# sheet1.net
KiCad netlist of a schematic drawn in Altium Designer
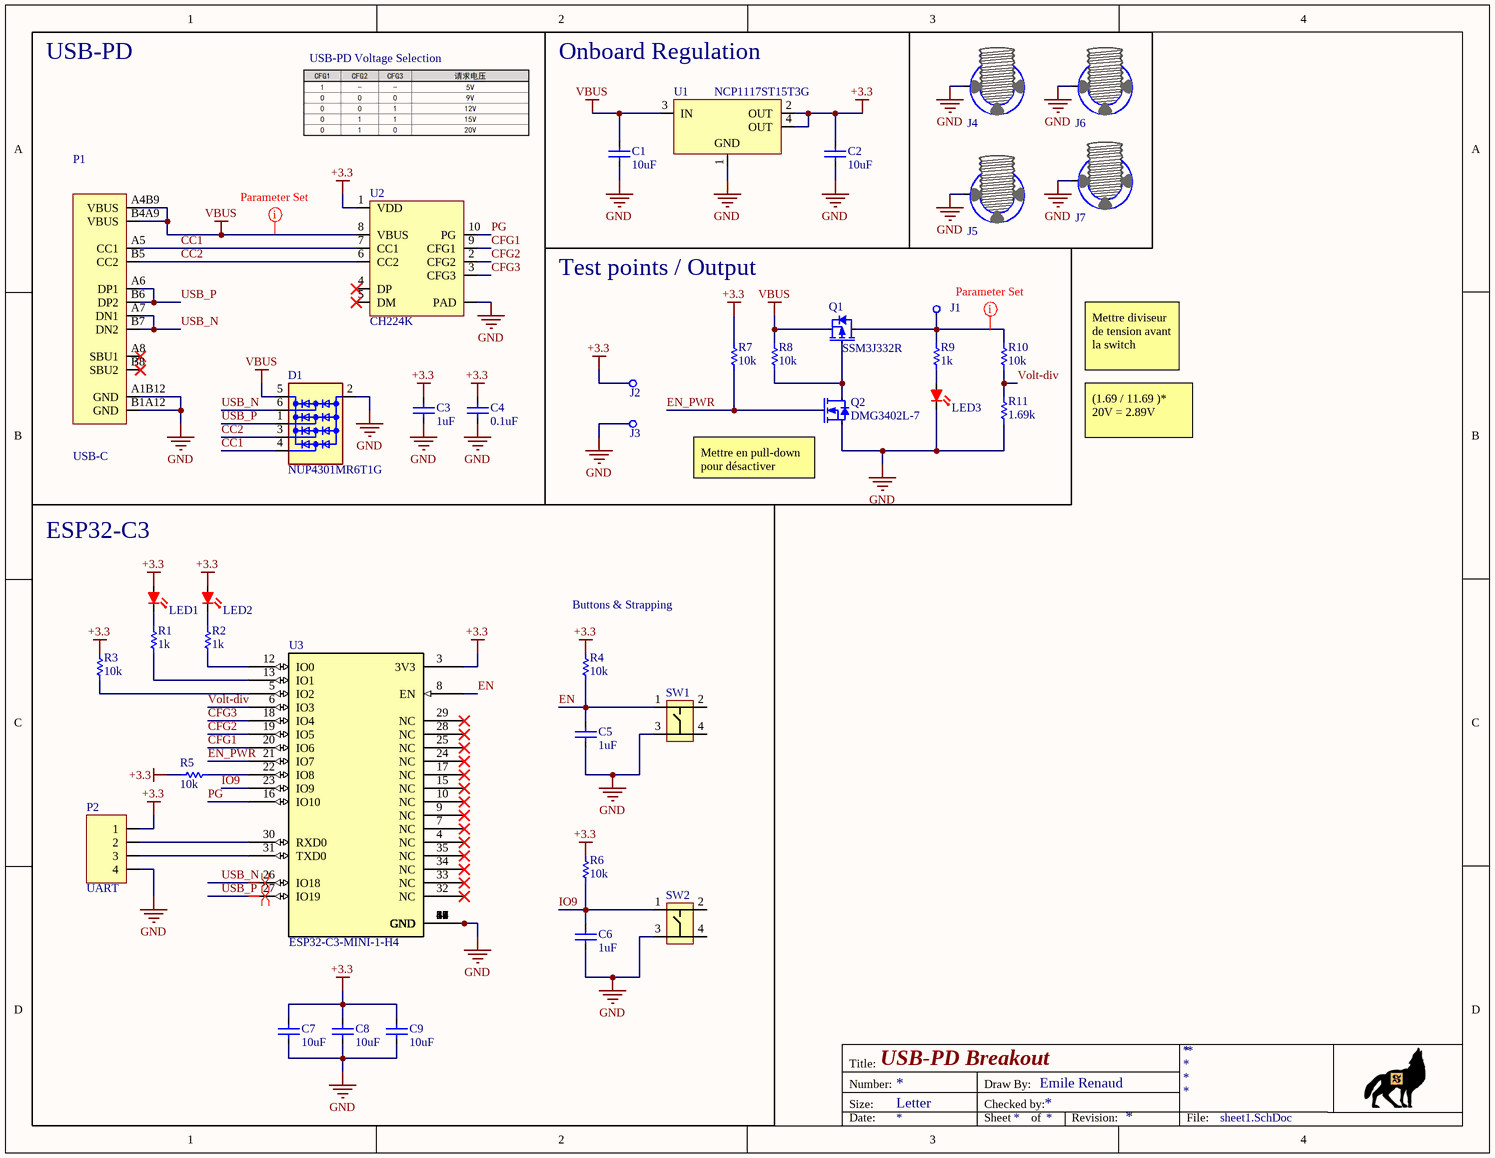
[diagram p0: sheet1.SchDoc]

(export (version "E")
  (design (tool "Eeschema 10.0.6"))
  (components
    (comp (ref "C1")
      (value "10uF")
      (footprint "CAPACITOR-0805")
      (description "Capacitor-0805-10uF-35V-X5R")
      (libsource (lib "Capacitors") (part "Capacitor-0805-10uF-35V-X5R"))
    )
    (comp (ref "C2")
      (value "10uF")
      (footprint "CAPACITOR-0805")
      (description "Capacitor-0805-10uF-35V-X5R")
      (libsource (lib "Capacitors") (part "Capacitor-0805-10uF-35V-X5R"))
    )
    (comp (ref "C3")
      (value "1uF")
      (footprint "CAPACITOR-0603")
      (description "Capacitor-0603-1uF-25V-X5R")
      (libsource (lib "Capacitors") (part "Capacitor-0603-1uF-25V-X5R"))
    )
    (comp (ref "C4")
      (value "0.1uF")
      (footprint "CAPACITOR-0603")
      (description "Capacitor-0603-0.1uF-50V-X7R")
      (libsource (lib "Capacitors") (part "Capacitor-0603-0.1uF-50V-X7R"))
    )
    (comp (ref "C5")
      (value "1uF")
      (footprint "CAPACITOR-0603")
      (description "Capacitor-0603-1uF-25V-X5R")
      (libsource (lib "Capacitors") (part "Capacitor-0603-1uF-25V-X5R"))
    )
    (comp (ref "C6")
      (value "1uF")
      (footprint "CAPACITOR-0603")
      (description "Capacitor-0603-1uF-25V-X5R")
      (libsource (lib "Capacitors") (part "Capacitor-0603-1uF-25V-X5R"))
    )
    (comp (ref "C7")
      (value "10uF")
      (footprint "CAPACITOR-0805")
      (description "Capacitor-0805-10uF-35V-X5R")
      (libsource (lib "Capacitors") (part "Capacitor-0805-10uF-35V-X5R"))
    )
    (comp (ref "C8")
      (value "10uF")
      (footprint "CAPACITOR-0805")
      (description "Capacitor-0805-10uF-35V-X5R")
      (libsource (lib "Capacitors") (part "Capacitor-0805-10uF-35V-X5R"))
    )
    (comp (ref "C9")
      (value "10uF")
      (footprint "CAPACITOR-0805")
      (description "Capacitor-0805-10uF-35V-X5R")
      (libsource (lib "Capacitors") (part "Capacitor-0805-10uF-35V-X5R"))
    )
    (comp (ref "D1")
      (value "NUP4301MR6T1G")
      (footprint "SOT-23-6")
      (description "4CH Clamp Ipp Tvs Diode Surface Mount SOT23-6 (SC74)")
      (libsource (lib "diodes") (part "NUP4301MR6T1G"))
    )
    (comp (ref "J1")
      (value "hole")
      (footprint "HOLE-2.70MM")
      (description "Hole for 12 AWG Stranded Wire")
      (libsource (lib "JumpersAndHoles") (part "Hole 2.70mm AWG12-Stranded"))
    )
    (comp (ref "J2")
      (value "hole")
      (footprint "HOLE-2.70MM")
      (description "Hole for 12 AWG Stranded Wire")
      (libsource (lib "JumpersAndHoles") (part "Hole 2.70mm AWG12-Stranded"))
    )
    (comp (ref "J3")
      (value "hole")
      (footprint "HOLE-2.70MM")
      (description "Hole for 12 AWG Stranded Wire")
      (libsource (lib "JumpersAndHoles") (part "Hole 2.70mm AWG12-Stranded"))
    )
    (comp (ref "J4")
      (value "hole")
      (footprint "HOLE-3.40MM-M3-7MMEYELET-MountingFeature")
      (description "Hole for M3 Bolt with 7mm pad")
      (libsource (lib "JumpersAndHoles") (part "Hole 3.40mm M3-MountingFeature"))
    )
    (comp (ref "J5")
      (value "hole")
      (footprint "HOLE-3.40MM-M3-7MMEYELET-MountingFeature")
      (description "Hole for M3 Bolt with 7mm pad")
      (libsource (lib "JumpersAndHoles") (part "Hole 3.40mm M3-MountingFeature"))
    )
    (comp (ref "J6")
      (value "hole")
      (footprint "HOLE-3.40MM-M3-7MMEYELET-MountingFeature")
      (description "Hole for M3 Bolt with 7mm pad")
      (libsource (lib "JumpersAndHoles") (part "Hole 3.40mm M3-MountingFeature"))
    )
    (comp (ref "J7")
      (value "hole")
      (footprint "HOLE-3.40MM-M3-7MMEYELET-MountingFeature")
      (description "Hole for M3 Bolt with 7mm pad")
      (libsource (lib "JumpersAndHoles") (part "Hole 3.40mm M3-MountingFeature"))
    )
    (comp (ref "LED1")
      (value "B1911USD-20D000114U1930")
      (footprint "LED-0603-2PIN")
      (description "LED RED CLEAR 1608 SMD")
      (libsource (lib "LEDs") (part "B1911USD-20D000114U1930"))
    )
    (comp (ref "LED2")
      (value "B1911USD-20D000114U1930")
      (footprint "LED-0603-2PIN")
      (description "LED RED CLEAR 1608 SMD")
      (libsource (lib "LEDs") (part "B1911USD-20D000114U1930"))
    )
    (comp (ref "LED3")
      (value "B1911USD-20D000114U1930")
      (footprint "LED-0603-2PIN")
      (description "LED RED CLEAR 1608 SMD")
      (libsource (lib "LEDs") (part "B1911USD-20D000114U1930"))
    )
    (comp (ref "P1")
      (value "USB-C")
      (footprint "USB-C")
      (description "TYPEC-304J-BCP16\r\n5A USB 3.1 1 Type-C SMD USB Connectors")
      (libsource (lib "PC-connector") (part "USB-C"))
    )
    (comp (ref "P2")
      (value "UART")
      (footprint "HDR1X4")
      (description "4pos TH 2.54mm Header")
      (libsource (lib "header") (part "4pos-TH-2.54mm"))
    )
    (comp (ref "Q1")
      (value "SSM3J332R")
      (footprint "SOT-23-3")
      (description "P-Channel 30 V 6A (Ta) 1W (Ta) Surface Mount SOT-23F")
      (libsource (lib "FET-P-Small") (part "SSM3J332R"))
    )
    (comp (ref "Q2")
      (value "DMG3402L-7")
      (footprint "SOT-23-3")
      (description "N-Channel 30 V 4A (Ta) 1.4W (Ta) Surface Mount SOT-23-3")
      (libsource (lib "FET-N-Small") (part "DMG3402L-7"))
    )
    (comp (ref "R1")
      (value "1k")
      (footprint "Resistor-0603")
      (description "Resistor0603-1k")
      (fields (field (name "Comment") "SMT resistor"))
      (libsource (lib "Resistors") (part "Resistor0603-1k"))
    )
    (comp (ref "R2")
      (value "1k")
      (footprint "Resistor-0603")
      (description "Resistor0603-1k")
      (fields (field (name "Comment") "SMT resistor"))
      (libsource (lib "Resistors") (part "Resistor0603-1k"))
    )
    (comp (ref "R3")
      (value "10k")
      (footprint "Resistor-0603")
      (description "Resistor0603-10k")
      (fields (field (name "Comment") "SMT resistor"))
      (libsource (lib "Resistors") (part "Resistor0603-10k"))
    )
    (comp (ref "R4")
      (value "10k")
      (footprint "Resistor-0603")
      (description "Resistor0603-10k")
      (fields (field (name "Comment") "SMT resistor"))
      (libsource (lib "Resistors") (part "Resistor0603-10k"))
    )
    (comp (ref "R5")
      (value "10k")
      (footprint "Resistor-0603")
      (description "Resistor0603-10k")
      (fields (field (name "Comment") "SMT resistor"))
      (libsource (lib "Resistors") (part "Resistor0603-10k"))
    )
    (comp (ref "R6")
      (value "10k")
      (footprint "Resistor-0603")
      (description "Resistor0603-10k")
      (fields (field (name "Comment") "SMT resistor"))
      (libsource (lib "Resistors") (part "Resistor0603-10k"))
    )
    (comp (ref "R7")
      (value "10k")
      (footprint "Resistor-0603")
      (description "Resistor0603-10k")
      (fields (field (name "Comment") "SMT resistor"))
      (libsource (lib "Resistors") (part "Resistor0603-10k"))
    )
    (comp (ref "R8")
      (value "10k")
      (footprint "Resistor-0603")
      (description "Resistor0603-10k")
      (fields (field (name "Comment") "SMT resistor"))
      (libsource (lib "Resistors") (part "Resistor0603-10k"))
    )
    (comp (ref "R9")
      (value "1k")
      (footprint "Resistor-0603")
      (description "Resistor0603-1k")
      (fields (field (name "Comment") "SMT resistor"))
      (libsource (lib "Resistors") (part "Resistor0603-1k"))
    )
    (comp (ref "R10")
      (value "10k")
      (footprint "Resistor-0603")
      (description "Resistor0603-10k")
      (fields (field (name "Comment") "SMT resistor"))
      (libsource (lib "Resistors") (part "Resistor0603-10k"))
    )
    (comp (ref "R11")
      (value "1.69k")
      (footprint "Resistor-0603")
      (description "Resistor0603-1.69k")
      (fields (field (name "Comment") "SMT resistor"))
      (libsource (lib "Resistors") (part "Resistor0603-1.69k"))
    )
    (comp (ref "SW1")
      (value "PTS815 SJM 250 SMTR LFS")
      (footprint "SW4_PTS815 SJM 250 SMTR LFS_CNK")
      (description "TACT 4.2 X 3.2, 2.5 MM H, 180GF,")
      (libsource (lib "THTPushButtonSwitches") (part "PTS815 SJM 250 SMTR LFS"))
    )
    (comp (ref "SW2")
      (value "PTS815 SJM 250 SMTR LFS")
      (footprint "SW4_PTS815 SJM 250 SMTR LFS_CNK")
      (description "TACT 4.2 X 3.2, 2.5 MM H, 180GF,")
      (libsource (lib "THTPushButtonSwitches") (part "PTS815 SJM 250 SMTR LFS"))
    )
    (comp (ref "U1")
      (value "NCP1117ST15T3G")
      (footprint "SOT-223-3/TO-261-3S")
      (description "IC REG LINEAR 3.3V 1A SOT223")
      (libsource (lib "PMIC-VoltageRegulators-LinearRegulators") (part "NCP1117ST15T3G"))
    )
    (comp (ref "U2")
      (value "CH224K")
      (footprint "SOP10-PAD")
      (description "IC USB-PD Controller \r\nESSOP-10")
      (libsource (lib "PMIC-USB") (part "CH224K"))
    )
    (comp (ref "U3")
      (value "ESP32-C3-MINI-1-H4")
      (footprint "ESP32-C3-MINI-1_EXP")
      (fields
        (field (name "MANUFACTURER_PART_NUMBER") "ESP32-C3-MINI-1-N4")
        (field (name "COPYRIGHT") "Copyright (C) 2023 Ultra Librarian. All rights reserved.")
      )
      (libsource (lib "Microcontrollers") (part "ESP32-C3-MINI-1-N4"))
    )
  )
  (nets
    (net (code "1") (name "+3.3") (class "Default")
      (node (ref "C2") (pin "2") (pinfunction "2_2") (pintype "passive"))
      (node (ref "C3") (pin "2") (pinfunction "2_2") (pintype "passive"))
      (node (ref "C4") (pin "2") (pinfunction "2_2") (pintype "passive"))
      (node (ref "C7") (pin "2") (pinfunction "2_2") (pintype "passive"))
      (node (ref "C8") (pin "2") (pinfunction "2_2") (pintype "passive"))
      (node (ref "C9") (pin "2") (pinfunction "2_2") (pintype "passive"))
      (node (ref "J2") (pin "1") (pinfunction "1_1") (pintype "passive"))
      (node (ref "LED1") (pin "2") (pinfunction "R_2") (pintype "passive"))
      (node (ref "LED2") (pin "2") (pinfunction "R_2") (pintype "passive"))
      (node (ref "P2") (pin "1") (pinfunction "1_1") (pintype "passive"))
      (node (ref "R3") (pin "2") (pinfunction "2_2") (pintype "passive"))
      (node (ref "R4") (pin "2") (pinfunction "2_2") (pintype "passive"))
      (node (ref "R5") (pin "2") (pinfunction "2_2") (pintype "passive"))
      (node (ref "R6") (pin "2") (pinfunction "2_2") (pintype "passive"))
      (node (ref "R7") (pin "2") (pinfunction "2_2") (pintype "passive"))
      (node (ref "U1") (pin "2") (pinfunction "OUT_2") (pintype "passive"))
      (node (ref "U1") (pin "4") (pinfunction "OUT_4") (pintype "passive"))
      (node (ref "U2") (pin "1") (pinfunction "VDD_1") (pintype "passive"))
      (node (ref "U3") (pin "3") (pinfunction "3V3_3") (pintype "power_in"))
    )
    (net (code "2") (name "/CC1") (class "Default")
      (node (ref "D1") (pin "4") (pinfunction "L4_4") (pintype "passive"))
      (node (ref "P1") (pin "A5") (pinfunction "CC1_A5") (pintype "passive"))
      (node (ref "U2") (pin "7") (pinfunction "CC1_7") (pintype "passive"))
    )
    (net (code "3") (name "/CC2") (class "Default")
      (node (ref "D1") (pin "3") (pinfunction "L3_3") (pintype "passive"))
      (node (ref "P1") (pin "B5") (pinfunction "CC2_B5") (pintype "passive"))
      (node (ref "U2") (pin "6") (pinfunction "CC2_6") (pintype "passive"))
    )
    (net (code "4") (name "/CFG1") (class "Default")
      (node (ref "U2") (pin "9") (pinfunction "CFG1_9") (pintype "passive"))
      (node (ref "U3") (pin "20") (pinfunction "IO6_20") (pintype "bidirectional"))
    )
    (net (code "5") (name "/CFG2") (class "Default")
      (node (ref "U2") (pin "2") (pinfunction "CFG2_2") (pintype "passive"))
      (node (ref "U3") (pin "19") (pinfunction "IO5_19") (pintype "bidirectional"))
    )
    (net (code "6") (name "/CFG3") (class "Default")
      (node (ref "U2") (pin "3") (pinfunction "CFG3_3") (pintype "passive"))
      (node (ref "U3") (pin "18") (pinfunction "IO4_18") (pintype "bidirectional"))
    )
    (net (code "7") (name "/EN") (class "Default")
      (node (ref "C5") (pin "2") (pinfunction "2_2") (pintype "passive"))
      (node (ref "R4") (pin "1") (pinfunction "1_1") (pintype "passive"))
      (node (ref "SW1") (pin "1") (pinfunction "1_1") (pintype "passive"))
      (node (ref "U3") (pin "8") (pinfunction "EN_8") (pintype "input"))
    )
    (net (code "8") (name "/EN_PWR") (class "Default")
      (node (ref "Q2") (pin "1") (pinfunction "G_1") (pintype "passive"))
      (node (ref "R7") (pin "1") (pinfunction "1_1") (pintype "passive"))
      (node (ref "U3") (pin "21") (pinfunction "IO7_21") (pintype "bidirectional"))
    )
    (net (code "9") (name "/IO9") (class "Default")
      (node (ref "C6") (pin "2") (pinfunction "2_2") (pintype "passive"))
      (node (ref "R6") (pin "1") (pinfunction "1_1") (pintype "passive"))
      (node (ref "SW2") (pin "1") (pinfunction "1_1") (pintype "passive"))
      (node (ref "U3") (pin "23") (pinfunction "IO9_23") (pintype "bidirectional"))
    )
    (net (code "10") (name "/PG") (class "Default")
      (node (ref "U2") (pin "10") (pinfunction "PG_10") (pintype "passive"))
      (node (ref "U3") (pin "16") (pinfunction "IO10_16") (pintype "bidirectional"))
    )
    (net (code "11") (name "/USB_N") (class "Default")
      (node (ref "D1") (pin "6") (pinfunction "L1_6") (pintype "passive"))
      (node (ref "P1") (pin "A7") (pinfunction "DN1_A7") (pintype "passive"))
      (node (ref "P1") (pin "B7") (pinfunction "DN2_B7") (pintype "passive"))
      (node (ref "U3") (pin "26") (pinfunction "IO18_26") (pintype "bidirectional"))
    )
    (net (code "12") (name "/USB_P") (class "Default")
      (node (ref "D1") (pin "1") (pinfunction "L2_1") (pintype "passive"))
      (node (ref "P1") (pin "A6") (pinfunction "DP1_A6") (pintype "passive"))
      (node (ref "P1") (pin "B6") (pinfunction "DP2_B6") (pintype "passive"))
      (node (ref "U3") (pin "27") (pinfunction "IO19_27") (pintype "bidirectional"))
    )
    (net (code "13") (name "/Volt-div") (class "Default")
      (node (ref "R10") (pin "1") (pinfunction "1_1") (pintype "passive"))
      (node (ref "R11") (pin "2") (pinfunction "2_2") (pintype "passive"))
      (node (ref "U3") (pin "6") (pinfunction "IO3_6") (pintype "bidirectional"))
    )
    (net (code "14") (name "GND") (class "Default")
      (node (ref "C1") (pin "1") (pinfunction "1_1") (pintype "passive"))
      (node (ref "C2") (pin "1") (pinfunction "1_1") (pintype "passive"))
      (node (ref "C3") (pin "1") (pinfunction "1_1") (pintype "passive"))
      (node (ref "C4") (pin "1") (pinfunction "1_1") (pintype "passive"))
      (node (ref "C5") (pin "1") (pinfunction "1_1") (pintype "passive"))
      (node (ref "C6") (pin "1") (pinfunction "1_1") (pintype "passive"))
      (node (ref "C7") (pin "1") (pinfunction "1_1") (pintype "passive"))
      (node (ref "C8") (pin "1") (pinfunction "1_1") (pintype "passive"))
      (node (ref "C9") (pin "1") (pinfunction "1_1") (pintype "passive"))
      (node (ref "D1") (pin "2") (pinfunction "GND_2") (pintype "passive"))
      (node (ref "J3") (pin "1") (pinfunction "1_1") (pintype "passive"))
      (node (ref "J4") (pin "1") (pinfunction "1_1") (pintype "passive"))
      (node (ref "J5") (pin "1") (pinfunction "1_1") (pintype "passive"))
      (node (ref "J6") (pin "1") (pinfunction "1_1") (pintype "passive"))
      (node (ref "J7") (pin "1") (pinfunction "1_1") (pintype "passive"))
      (node (ref "LED3") (pin "1") (pinfunction "K_1") (pintype "passive"))
      (node (ref "P1") (pin "A1B12") (pinfunction "GND_A1B12") (pintype "passive"))
      (node (ref "P1") (pin "B1A12") (pinfunction "GND_B1A12") (pintype "passive"))
      (node (ref "P2") (pin "4") (pinfunction "4_4") (pintype "passive"))
      (node (ref "Q2") (pin "2") (pinfunction "S_2") (pintype "passive"))
      (node (ref "R11") (pin "1") (pinfunction "1_1") (pintype "passive"))
      (node (ref "SW1") (pin "3") (pinfunction "3_3") (pintype "passive"))
      (node (ref "SW2") (pin "3") (pinfunction "3_3") (pintype "passive"))
      (node (ref "U1") (pin "1") (pinfunction "GND_1") (pintype "passive"))
      (node (ref "U2") (pin "PAD") (pinfunction "PAD_PAD") (pintype "passive"))
      (node (ref "U3") (pin "1") (pinfunction "GND_1") (pintype "passive"))
      (node (ref "U3") (pin "11") (pinfunction "GND_11") (pintype "passive"))
      (node (ref "U3") (pin "14") (pinfunction "GND_14") (pintype "passive"))
      (node (ref "U3") (pin "2") (pinfunction "GND_2") (pintype "passive"))
      (node (ref "U3") (pin "36") (pinfunction "GND_36") (pintype "passive"))
      (node (ref "U3") (pin "37") (pinfunction "GND_37") (pintype "passive"))
      (node (ref "U3") (pin "38") (pinfunction "GND_38") (pintype "passive"))
      (node (ref "U3") (pin "39") (pinfunction "GND_39") (pintype "passive"))
      (node (ref "U3") (pin "40") (pinfunction "GND_40") (pintype "passive"))
      (node (ref "U3") (pin "41") (pinfunction "GND_41") (pintype "passive"))
      (node (ref "U3") (pin "42") (pinfunction "GND_42") (pintype "passive"))
      (node (ref "U3") (pin "43") (pinfunction "GND_43") (pintype "passive"))
      (node (ref "U3") (pin "44") (pinfunction "GND_44") (pintype "passive"))
      (node (ref "U3") (pin "45") (pinfunction "GND_45") (pintype "passive"))
      (node (ref "U3") (pin "46") (pinfunction "GND_46") (pintype "passive"))
      (node (ref "U3") (pin "47") (pinfunction "GND_47") (pintype "passive"))
      (node (ref "U3") (pin "48") (pinfunction "GND_48") (pintype "passive"))
      (node (ref "U3") (pin "49") (pinfunction "GND_49") (pintype "passive"))
      (node (ref "U3") (pin "50") (pinfunction "GND_50") (pintype "passive"))
      (node (ref "U3") (pin "51") (pinfunction "GND_51") (pintype "passive"))
      (node (ref "U3") (pin "52") (pinfunction "GND_52") (pintype "passive"))
      (node (ref "U3") (pin "53") (pinfunction "GND_53") (pintype "passive"))
      (node (ref "U3") (pin "54") (pinfunction "GND_54") (pintype "passive"))
      (node (ref "U3") (pin "55") (pinfunction "GND_55") (pintype "passive"))
      (node (ref "U3") (pin "56") (pinfunction "GND_56") (pintype "passive"))
      (node (ref "U3") (pin "57") (pinfunction "GND_57") (pintype "passive"))
      (node (ref "U3") (pin "58") (pinfunction "GND_58") (pintype "passive"))
      (node (ref "U3") (pin "59") (pinfunction "GND_59") (pintype "passive"))
      (node (ref "U3") (pin "60") (pinfunction "GND_60") (pintype "passive"))
      (node (ref "U3") (pin "61") (pinfunction "GND_61") (pintype "passive"))
    )
    (net (code "15") (name "Net-(LED1-K)") (class "Default")
      (node (ref "LED1") (pin "1") (pinfunction "K_1") (pintype "passive"))
      (node (ref "R1") (pin "2") (pinfunction "2_2") (pintype "passive"))
    )
    (net (code "16") (name "Net-(LED2-K)") (class "Default")
      (node (ref "LED2") (pin "1") (pinfunction "K_1") (pintype "passive"))
      (node (ref "R2") (pin "2") (pinfunction "2_2") (pintype "passive"))
    )
    (net (code "17") (name "Net-(LED3-R)") (class "Default")
      (node (ref "LED3") (pin "2") (pinfunction "R_2") (pintype "passive"))
      (node (ref "R9") (pin "1") (pinfunction "1_1") (pintype "passive"))
    )
    (net (code "18") (name "Net-(Q1-D)") (class "Default")
      (node (ref "J1") (pin "1") (pinfunction "1_1") (pintype "passive"))
      (node (ref "Q1") (pin "3") (pinfunction "D_3") (pintype "passive"))
      (node (ref "R10") (pin "2") (pinfunction "2_2") (pintype "passive"))
      (node (ref "R9") (pin "2") (pinfunction "2_2") (pintype "passive"))
    )
    (net (code "19") (name "Net-(Q1-G)") (class "Default")
      (node (ref "Q1") (pin "1") (pinfunction "G_1") (pintype "passive"))
      (node (ref "Q2") (pin "3") (pinfunction "D_3") (pintype "passive"))
      (node (ref "R8") (pin "1") (pinfunction "1_1") (pintype "passive"))
    )
    (net (code "20") (name "Net-(U3-IO0)") (class "Default")
      (node (ref "R2") (pin "1") (pinfunction "1_1") (pintype "passive"))
      (node (ref "U3") (pin "12") (pinfunction "IO0_12") (pintype "bidirectional"))
    )
    (net (code "21") (name "Net-(U3-IO1)") (class "Default")
      (node (ref "R1") (pin "1") (pinfunction "1_1") (pintype "passive"))
      (node (ref "U3") (pin "13") (pinfunction "IO1_13") (pintype "bidirectional"))
    )
    (net (code "22") (name "Net-(U3-IO2)") (class "Default")
      (node (ref "R3") (pin "1") (pinfunction "1_1") (pintype "passive"))
      (node (ref "U3") (pin "5") (pinfunction "IO2_5") (pintype "bidirectional"))
    )
    (net (code "23") (name "Net-(U3-IO8)") (class "Default")
      (node (ref "R5") (pin "1") (pinfunction "1_1") (pintype "passive"))
      (node (ref "U3") (pin "22") (pinfunction "IO8_22") (pintype "bidirectional"))
    )
    (net (code "24") (name "Net-(U3-RXD0)") (class "Default")
      (node (ref "P2") (pin "2") (pinfunction "2_2") (pintype "passive"))
      (node (ref "U3") (pin "30") (pinfunction "RXD0_30") (pintype "bidirectional"))
    )
    (net (code "25") (name "Net-(U3-TXD0)") (class "Default")
      (node (ref "P2") (pin "3") (pinfunction "3_3") (pintype "passive"))
      (node (ref "U3") (pin "31") (pinfunction "TXD0_31") (pintype "bidirectional"))
    )
    (net (code "26") (name "VBUS") (class "Default")
      (node (ref "C1") (pin "2") (pinfunction "2_2") (pintype "passive"))
      (node (ref "D1") (pin "5") (pinfunction "VDD_5") (pintype "passive"))
      (node (ref "P1") (pin "A4B9") (pinfunction "VBUS_A4B9") (pintype "passive"))
      (node (ref "P1") (pin "B4A9") (pinfunction "VBUS_B4A9") (pintype "passive"))
      (node (ref "Q1") (pin "2") (pinfunction "S_2") (pintype "passive"))
      (node (ref "R8") (pin "2") (pinfunction "2_2") (pintype "passive"))
      (node (ref "U1") (pin "3") (pinfunction "IN_3") (pintype "passive"))
      (node (ref "U2") (pin "8") (pinfunction "VBUS_8") (pintype "passive"))
    )
    (net (code "27") (name "unconnected-(P1-SBU1-PadA8)") (class "Default")
      (node (ref "P1") (pin "A8") (pinfunction "SBU1_A8") (pintype "passive+no_connect"))
    )
    (net (code "28") (name "unconnected-(P1-SBU2-PadB8)") (class "Default")
      (node (ref "P1") (pin "B8") (pinfunction "SBU2_B8") (pintype "passive+no_connect"))
    )
    (net (code "29") (name "unconnected-(SW1-Pad2)") (class "Default")
      (node (ref "SW1") (pin "2") (pinfunction "2_2") (pintype "passive"))
    )
    (net (code "30") (name "unconnected-(SW1-Pad4)") (class "Default")
      (node (ref "SW1") (pin "4") (pinfunction "4_4") (pintype "passive"))
    )
    (net (code "31") (name "unconnected-(SW2-Pad2)") (class "Default")
      (node (ref "SW2") (pin "2") (pinfunction "2_2") (pintype "passive"))
    )
    (net (code "32") (name "unconnected-(SW2-Pad4)") (class "Default")
      (node (ref "SW2") (pin "4") (pinfunction "4_4") (pintype "passive"))
    )
    (net (code "33") (name "unconnected-(U2-DM-Pad5)") (class "Default")
      (node (ref "U2") (pin "5") (pinfunction "DM_5") (pintype "passive+no_connect"))
    )
    (net (code "34") (name "unconnected-(U2-DP-Pad4)") (class "Default")
      (node (ref "U2") (pin "4") (pinfunction "DP_4") (pintype "passive+no_connect"))
    )
    (net (code "35") (name "unconnected-(U3-NC-Pad4)") (class "Default")
      (node (ref "U3") (pin "4") (pinfunction "NC_4") (pintype "passive+no_connect"))
    )
    (net (code "36") (name "unconnected-(U3-NC-Pad7)") (class "Default")
      (node (ref "U3") (pin "7") (pinfunction "NC_7") (pintype "passive+no_connect"))
    )
    (net (code "37") (name "unconnected-(U3-NC-Pad9)") (class "Default")
      (node (ref "U3") (pin "9") (pinfunction "NC_9") (pintype "passive+no_connect"))
    )
    (net (code "38") (name "unconnected-(U3-NC-Pad10)") (class "Default")
      (node (ref "U3") (pin "10") (pinfunction "NC_10") (pintype "passive+no_connect"))
    )
    (net (code "39") (name "unconnected-(U3-NC-Pad15)") (class "Default")
      (node (ref "U3") (pin "15") (pinfunction "NC_15") (pintype "passive+no_connect"))
    )
    (net (code "40") (name "unconnected-(U3-NC-Pad17)") (class "Default")
      (node (ref "U3") (pin "17") (pinfunction "NC_17") (pintype "passive+no_connect"))
    )
    (net (code "41") (name "unconnected-(U3-NC-Pad24)") (class "Default")
      (node (ref "U3") (pin "24") (pinfunction "NC_24") (pintype "passive+no_connect"))
    )
    (net (code "42") (name "unconnected-(U3-NC-Pad25)") (class "Default")
      (node (ref "U3") (pin "25") (pinfunction "NC_25") (pintype "passive+no_connect"))
    )
    (net (code "43") (name "unconnected-(U3-NC-Pad28)") (class "Default")
      (node (ref "U3") (pin "28") (pinfunction "NC_28") (pintype "passive+no_connect"))
    )
    (net (code "44") (name "unconnected-(U3-NC-Pad29)") (class "Default")
      (node (ref "U3") (pin "29") (pinfunction "NC_29") (pintype "passive+no_connect"))
    )
    (net (code "45") (name "unconnected-(U3-NC-Pad32)") (class "Default")
      (node (ref "U3") (pin "32") (pinfunction "NC_32") (pintype "passive+no_connect"))
    )
    (net (code "46") (name "unconnected-(U3-NC-Pad33)") (class "Default")
      (node (ref "U3") (pin "33") (pinfunction "NC_33") (pintype "passive+no_connect"))
    )
    (net (code "47") (name "unconnected-(U3-NC-Pad34)") (class "Default")
      (node (ref "U3") (pin "34") (pinfunction "NC_34") (pintype "passive+no_connect"))
    )
    (net (code "48") (name "unconnected-(U3-NC-Pad35)") (class "Default")
      (node (ref "U3") (pin "35") (pinfunction "NC_35") (pintype "passive+no_connect"))
    )
  )
)
